# Sheet1.net
KiCad netlist of a schematic drawn in Altium Designer
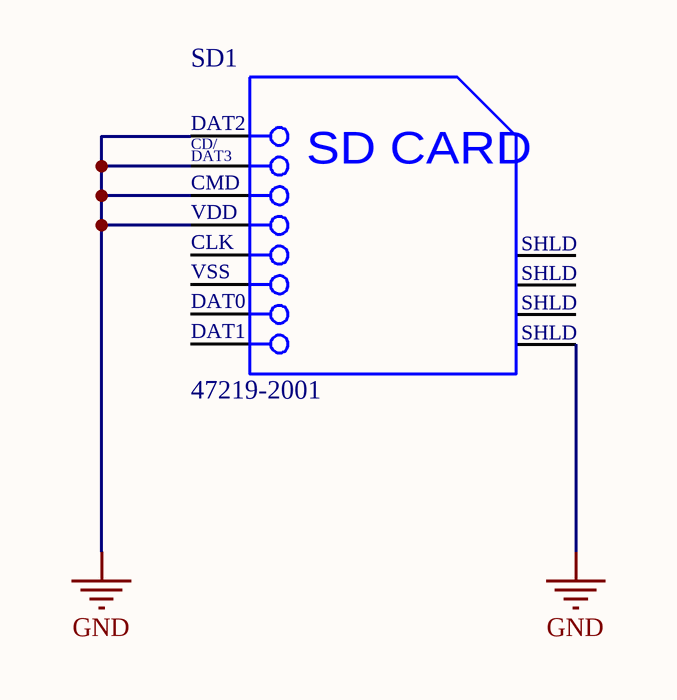
[diagram p0: Sheet1.SchDoc]

(export (version "E")
  (design (tool "Eeschema 10.0.6"))
  (components
    (comp (ref "SD1")
      (value "47219-2001")
      (footprint "MOLX-47219-2001-8_V")
      (description "MicroSD Card Connector, Hinge Type, -40 to 85 degC, 8-Pin SMD, RoHS, Tape and Reel")
      (fields (field (name "MANUFACTURER") "Molex"))
      (libsource (lib "Altium Content Vault") (part "CN-SD-8-4S"))
    )
  )
  (nets
    (net (code "1") (name "GND") (class "Default")
      (node (ref "SD1") (pin "1") (pinfunction "DAT2_1") (pintype "passive"))
      (node (ref "SD1") (pin "12") (pinfunction "SHLD_12") (pintype "passive"))
      (node (ref "SD1") (pin "2") (pinfunction "CD/DAT3_2") (pintype "passive"))
      (node (ref "SD1") (pin "3") (pinfunction "CMD_3") (pintype "passive"))
      (node (ref "SD1") (pin "4") (pinfunction "VDD_4") (pintype "passive"))
    )
    (net (code "2") (name "unconnected-(SD1-CLK-Pad5)") (class "Default")
      (node (ref "SD1") (pin "5") (pinfunction "CLK_5") (pintype "passive"))
    )
    (net (code "3") (name "unconnected-(SD1-DAT0-Pad7)") (class "Default")
      (node (ref "SD1") (pin "7") (pinfunction "DAT0_7") (pintype "passive"))
    )
    (net (code "4") (name "unconnected-(SD1-DAT1-Pad8)") (class "Default")
      (node (ref "SD1") (pin "8") (pinfunction "DAT1_8") (pintype "passive"))
    )
    (net (code "5") (name "unconnected-(SD1-SHLD-Pad9)") (class "Default")
      (node (ref "SD1") (pin "9") (pinfunction "SHLD_9") (pintype "passive"))
    )
    (net (code "6") (name "unconnected-(SD1-SHLD-Pad10)") (class "Default")
      (node (ref "SD1") (pin "10") (pinfunction "SHLD_10") (pintype "passive"))
    )
    (net (code "7") (name "unconnected-(SD1-SHLD-Pad11)") (class "Default")
      (node (ref "SD1") (pin "11") (pinfunction "SHLD_11") (pintype "passive"))
    )
    (net (code "8") (name "unconnected-(SD1-VSS-Pad6)") (class "Default")
      (node (ref "SD1") (pin "6") (pinfunction "VSS_6") (pintype "passive"))
    )
  )
)
